# Madhumathimmiv_8-bit-breadboard-computer.net
KiCad netlist of a schematic drawn in Altium Designer
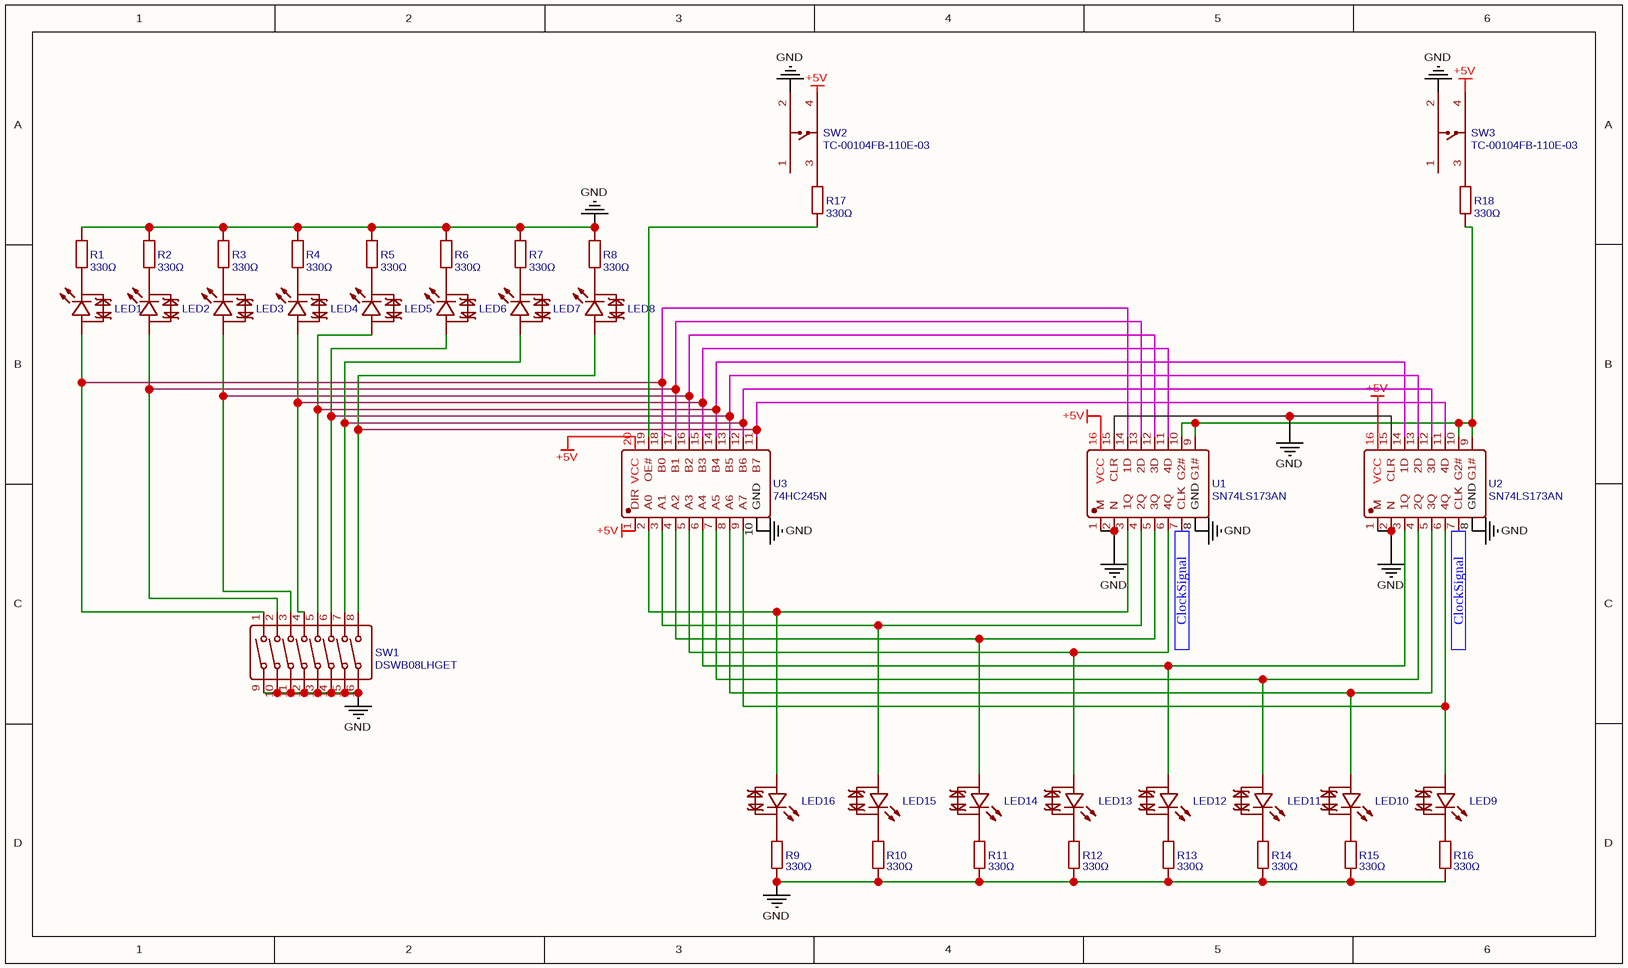
[diagram p0: Madhumathimmiv_8-bit-breadboard-computer-modules__schematic_Register__register.schdoc]

(export (version "E")
  (design (tool "Eeschema 10.0.6"))
  (components
    (comp (ref "LED1")
      (value "204-15UTC/S400-X9-L")
      (fields (field (name "MANUFACTURER") "EVERLIGHT(亿光)") (field (name "CONTRIBUTOR") "LCSC"))
      (libsource (lib "altium-import") (part "root_1_204-15UTC/S400-X9-L_"))
    )
    (comp (ref "LED2")
      (value "204-15UTC/S400-X9-L")
      (fields (field (name "MANUFACTURER") "EVERLIGHT(亿光)") (field (name "CONTRIBUTOR") "LCSC"))
      (libsource (lib "altium-import") (part "root_1_204-15UTC/S400-X9-L_"))
    )
    (comp (ref "LED3")
      (value "204-15UTC/S400-X9-L")
      (fields (field (name "MANUFACTURER") "EVERLIGHT(亿光)") (field (name "CONTRIBUTOR") "LCSC"))
      (libsource (lib "altium-import") (part "root_1_204-15UTC/S400-X9-L_"))
    )
    (comp (ref "LED4")
      (value "204-15UTC/S400-X9-L")
      (fields (field (name "MANUFACTURER") "EVERLIGHT(亿光)") (field (name "CONTRIBUTOR") "LCSC"))
      (libsource (lib "altium-import") (part "root_1_204-15UTC/S400-X9-L_"))
    )
    (comp (ref "LED5")
      (value "204-15UTC/S400-X9-L")
      (fields (field (name "MANUFACTURER") "EVERLIGHT(亿光)") (field (name "CONTRIBUTOR") "LCSC"))
      (libsource (lib "altium-import") (part "root_1_204-15UTC/S400-X9-L_"))
    )
    (comp (ref "LED6")
      (value "204-15UTC/S400-X9-L")
      (fields (field (name "MANUFACTURER") "EVERLIGHT(亿光)") (field (name "CONTRIBUTOR") "LCSC"))
      (libsource (lib "altium-import") (part "root_1_204-15UTC/S400-X9-L_"))
    )
    (comp (ref "LED7")
      (value "204-15UTC/S400-X9-L")
      (fields (field (name "MANUFACTURER") "EVERLIGHT(亿光)") (field (name "CONTRIBUTOR") "LCSC"))
      (libsource (lib "altium-import") (part "root_1_204-15UTC/S400-X9-L_"))
    )
    (comp (ref "LED8")
      (value "204-15UTC/S400-X9-L")
      (fields (field (name "MANUFACTURER") "EVERLIGHT(亿光)") (field (name "CONTRIBUTOR") "LCSC"))
      (libsource (lib "altium-import") (part "root_1_204-15UTC/S400-X9-L_"))
    )
    (comp (ref "LED9")
      (value "204-15UTC/S400-X9-L")
      (fields (field (name "MANUFACTURER") "EVERLIGHT(亿光)") (field (name "CONTRIBUTOR") "LCSC"))
      (libsource (lib "altium-import") (part "root_3_204-15UTC/S400-X9-L_"))
    )
    (comp (ref "LED10")
      (value "204-15UTC/S400-X9-L")
      (fields (field (name "MANUFACTURER") "EVERLIGHT(亿光)") (field (name "CONTRIBUTOR") "LCSC"))
      (libsource (lib "altium-import") (part "root_3_204-15UTC/S400-X9-L_"))
    )
    (comp (ref "LED11")
      (value "204-15UTC/S400-X9-L")
      (fields (field (name "MANUFACTURER") "EVERLIGHT(亿光)") (field (name "CONTRIBUTOR") "LCSC"))
      (libsource (lib "altium-import") (part "root_3_204-15UTC/S400-X9-L_"))
    )
    (comp (ref "LED12")
      (value "204-15UTC/S400-X9-L")
      (fields (field (name "MANUFACTURER") "EVERLIGHT(亿光)") (field (name "CONTRIBUTOR") "LCSC"))
      (libsource (lib "altium-import") (part "root_3_204-15UTC/S400-X9-L_"))
    )
    (comp (ref "LED13")
      (value "204-15UTC/S400-X9-L")
      (fields (field (name "MANUFACTURER") "EVERLIGHT(亿光)") (field (name "CONTRIBUTOR") "LCSC"))
      (libsource (lib "altium-import") (part "root_3_204-15UTC/S400-X9-L_"))
    )
    (comp (ref "LED14")
      (value "204-15UTC/S400-X9-L")
      (fields (field (name "MANUFACTURER") "EVERLIGHT(亿光)") (field (name "CONTRIBUTOR") "LCSC"))
      (libsource (lib "altium-import") (part "root_3_204-15UTC/S400-X9-L_"))
    )
    (comp (ref "LED15")
      (value "204-15UTC/S400-X9-L")
      (fields (field (name "MANUFACTURER") "EVERLIGHT(亿光)") (field (name "CONTRIBUTOR") "LCSC"))
      (libsource (lib "altium-import") (part "root_3_204-15UTC/S400-X9-L_"))
    )
    (comp (ref "LED16")
      (value "204-15UTC/S400-X9-L")
      (fields (field (name "MANUFACTURER") "EVERLIGHT(亿光)") (field (name "CONTRIBUTOR") "LCSC"))
      (libsource (lib "altium-import") (part "root_3_204-15UTC/S400-X9-L_"))
    )
    (comp (ref "R1")
      (value "330Ω")
      (fields
        (field (name "MANUFACTURER") "CCO(千志电子)")
        (field (name "MANUFACTURER PART") "MF1/2W-0.1Ω±1% T")
        (field (name "CONTRIBUTOR") "LCSC")
      )
      (libsource (lib "altium-import") (part "root_1_330Ω_"))
    )
    (comp (ref "R2")
      (value "330Ω")
      (fields
        (field (name "MANUFACTURER") "CCO(千志电子)")
        (field (name "MANUFACTURER PART") "MF1/2W-0.1Ω±1% T")
        (field (name "CONTRIBUTOR") "LCSC")
      )
      (libsource (lib "altium-import") (part "root_1_330Ω_"))
    )
    (comp (ref "R3")
      (value "330Ω")
      (fields
        (field (name "MANUFACTURER") "CCO(千志电子)")
        (field (name "MANUFACTURER PART") "MF1/2W-0.1Ω±1% T")
        (field (name "CONTRIBUTOR") "LCSC")
      )
      (libsource (lib "altium-import") (part "root_1_330Ω_"))
    )
    (comp (ref "R4")
      (value "330Ω")
      (fields
        (field (name "MANUFACTURER") "CCO(千志电子)")
        (field (name "MANUFACTURER PART") "MF1/2W-0.1Ω±1% T")
        (field (name "CONTRIBUTOR") "LCSC")
      )
      (libsource (lib "altium-import") (part "root_1_330Ω_"))
    )
    (comp (ref "R5")
      (value "330Ω")
      (fields
        (field (name "MANUFACTURER") "CCO(千志电子)")
        (field (name "MANUFACTURER PART") "MF1/2W-0.1Ω±1% T")
        (field (name "CONTRIBUTOR") "LCSC")
      )
      (libsource (lib "altium-import") (part "root_1_330Ω_"))
    )
    (comp (ref "R6")
      (value "330Ω")
      (fields
        (field (name "MANUFACTURER") "CCO(千志电子)")
        (field (name "MANUFACTURER PART") "MF1/2W-0.1Ω±1% T")
        (field (name "CONTRIBUTOR") "LCSC")
      )
      (libsource (lib "altium-import") (part "root_1_330Ω_"))
    )
    (comp (ref "R7")
      (value "330Ω")
      (fields
        (field (name "MANUFACTURER") "CCO(千志电子)")
        (field (name "MANUFACTURER PART") "MF1/2W-0.1Ω±1% T")
        (field (name "CONTRIBUTOR") "LCSC")
      )
      (libsource (lib "altium-import") (part "root_1_330Ω_"))
    )
    (comp (ref "R8")
      (value "330Ω")
      (fields
        (field (name "MANUFACTURER") "CCO(千志电子)")
        (field (name "MANUFACTURER PART") "MF1/2W-0.1Ω±1% T")
        (field (name "CONTRIBUTOR") "LCSC")
      )
      (libsource (lib "altium-import") (part "root_1_330Ω_"))
    )
    (comp (ref "R9")
      (value "330Ω")
      (fields
        (field (name "MANUFACTURER") "CCO(千志电子)")
        (field (name "MANUFACTURER PART") "MF1/2W-0.1Ω±1% T")
        (field (name "CONTRIBUTOR") "LCSC")
      )
      (libsource (lib "altium-import") (part "root_3_330Ω_"))
    )
    (comp (ref "R10")
      (value "330Ω")
      (fields
        (field (name "MANUFACTURER") "CCO(千志电子)")
        (field (name "MANUFACTURER PART") "MF1/2W-0.1Ω±1% T")
        (field (name "CONTRIBUTOR") "LCSC")
      )
      (libsource (lib "altium-import") (part "root_3_330Ω_"))
    )
    (comp (ref "R11")
      (value "330Ω")
      (fields
        (field (name "MANUFACTURER") "CCO(千志电子)")
        (field (name "MANUFACTURER PART") "MF1/2W-0.1Ω±1% T")
        (field (name "CONTRIBUTOR") "LCSC")
      )
      (libsource (lib "altium-import") (part "root_3_330Ω_"))
    )
    (comp (ref "R12")
      (value "330Ω")
      (fields
        (field (name "MANUFACTURER") "CCO(千志电子)")
        (field (name "MANUFACTURER PART") "MF1/2W-0.1Ω±1% T")
        (field (name "CONTRIBUTOR") "LCSC")
      )
      (libsource (lib "altium-import") (part "root_3_330Ω_"))
    )
    (comp (ref "R13")
      (value "330Ω")
      (fields
        (field (name "MANUFACTURER") "CCO(千志电子)")
        (field (name "MANUFACTURER PART") "MF1/2W-0.1Ω±1% T")
        (field (name "CONTRIBUTOR") "LCSC")
      )
      (libsource (lib "altium-import") (part "root_3_330Ω_"))
    )
    (comp (ref "R14")
      (value "330Ω")
      (fields
        (field (name "MANUFACTURER") "CCO(千志电子)")
        (field (name "MANUFACTURER PART") "MF1/2W-0.1Ω±1% T")
        (field (name "CONTRIBUTOR") "LCSC")
      )
      (libsource (lib "altium-import") (part "root_3_330Ω_"))
    )
    (comp (ref "R15")
      (value "330Ω")
      (fields
        (field (name "MANUFACTURER") "CCO(千志电子)")
        (field (name "MANUFACTURER PART") "MF1/2W-0.1Ω±1% T")
        (field (name "CONTRIBUTOR") "LCSC")
      )
      (libsource (lib "altium-import") (part "root_3_330Ω_"))
    )
    (comp (ref "R16")
      (value "330Ω")
      (fields
        (field (name "MANUFACTURER") "CCO(千志电子)")
        (field (name "MANUFACTURER PART") "MF1/2W-0.1Ω±1% T")
        (field (name "CONTRIBUTOR") "LCSC")
      )
      (libsource (lib "altium-import") (part "root_3_330Ω_"))
    )
    (comp (ref "R17")
      (value "330Ω")
      (fields
        (field (name "MANUFACTURER") "CCO(千志电子)")
        (field (name "MANUFACTURER PART") "MF1/2W-0.1Ω±1% T")
        (field (name "CONTRIBUTOR") "LCSC")
      )
      (libsource (lib "altium-import") (part "root_1_330Ω_"))
    )
    (comp (ref "R18")
      (value "330Ω")
      (fields
        (field (name "MANUFACTURER") "CCO(千志电子)")
        (field (name "MANUFACTURER PART") "MF1/2W-0.1Ω±1% T")
        (field (name "CONTRIBUTOR") "LCSC")
      )
      (libsource (lib "altium-import") (part "root_1_330Ω_"))
    )
    (comp (ref "SW1")
      (value "DSWB08LHGET")
      (fields (field (name "MANUFACTURER") "YE") (field (name "CONTRIBUTOR") "LCSC"))
      (libsource (lib "altium-import") (part "root_0_DSWB08LHGET_"))
    )
    (comp (ref "SW2")
      (value "TC-00104FB-110E-03")
      (fields (field (name "MANUFACTURER") "HOOYA(皓宇电子)") (field (name "CONTRIBUTOR") "lcsc"))
      (libsource (lib "altium-import") (part "root_1_TC-00104FB-110E-03_"))
    )
    (comp (ref "SW3")
      (value "TC-00104FB-110E-03")
      (fields (field (name "MANUFACTURER") "HOOYA(皓宇电子)") (field (name "CONTRIBUTOR") "lcsc"))
      (libsource (lib "altium-import") (part "root_1_TC-00104FB-110E-03_"))
    )
    (comp (ref "U1")
      (value "SN74LS173AN")
      (fields (field (name "MANUFACTURER") "TI(德州仪器)") (field (name "CONTRIBUTOR") "LCSC"))
      (libsource (lib "altium-import") (part "root_1_SN74LS173AN_"))
    )
    (comp (ref "U2")
      (value "SN74LS173AN")
      (fields (field (name "MANUFACTURER") "TI(德州仪器)") (field (name "CONTRIBUTOR") "LCSC"))
      (libsource (lib "altium-import") (part "root_1_SN74LS173AN_"))
    )
    (comp (ref "U3")
      (value "74HC245N")
      (fields (field (name "MANUFACTURER") "HGSEMI(华冠)") (field (name "CONTRIBUTOR") "LCSC"))
      (libsource (lib "altium-import") (part "root_1_74HC245N_"))
    )
  )
  (nets
    (net (code "1") (name "+5V") (class "Default")
      (node (ref "SW3") (pin "4") (pinfunction "4_4") (pintype "passive"))
      (node (ref "U1") (pin "16") (pinfunction "VCC_16") (pintype "passive"))
      (node (ref "U2") (pin "16") (pinfunction "VCC_16") (pintype "passive"))
      (node (ref "U3") (pin "1") (pinfunction "DIR_1") (pintype "passive"))
      (node (ref "U3") (pin "20") (pinfunction "VCC_20") (pintype "passive"))
    )
    (net (code "2") (name "/ClockSignal") (class "Default")
      (node (ref "U1") (pin "7") (pinfunction "CLK_7") (pintype "passive"))
      (node (ref "U2") (pin "7") (pinfunction "CLK_7") (pintype "passive"))
    )
    (net (code "3") (name "GND") (class "Default")
      (node (ref "R1") (pin "2") (pinfunction "2_2") (pintype "passive"))
      (node (ref "R10") (pin "2") (pinfunction "2_2") (pintype "passive"))
      (node (ref "R11") (pin "2") (pinfunction "2_2") (pintype "passive"))
      (node (ref "R12") (pin "2") (pinfunction "2_2") (pintype "passive"))
      (node (ref "R13") (pin "2") (pinfunction "2_2") (pintype "passive"))
      (node (ref "R14") (pin "2") (pinfunction "2_2") (pintype "passive"))
      (node (ref "R15") (pin "2") (pinfunction "2_2") (pintype "passive"))
      (node (ref "R16") (pin "2") (pinfunction "2_2") (pintype "passive"))
      (node (ref "R2") (pin "2") (pinfunction "2_2") (pintype "passive"))
      (node (ref "R3") (pin "2") (pinfunction "2_2") (pintype "passive"))
      (node (ref "R4") (pin "2") (pinfunction "2_2") (pintype "passive"))
      (node (ref "R5") (pin "2") (pinfunction "2_2") (pintype "passive"))
      (node (ref "R6") (pin "2") (pinfunction "2_2") (pintype "passive"))
      (node (ref "R7") (pin "2") (pinfunction "2_2") (pintype "passive"))
      (node (ref "R8") (pin "2") (pinfunction "2_2") (pintype "passive"))
      (node (ref "R9") (pin "2") (pinfunction "2_2") (pintype "passive"))
      (node (ref "SW1") (pin "10") (pinfunction "10_10") (pintype "passive"))
      (node (ref "SW1") (pin "11") (pinfunction "11_11") (pintype "passive"))
      (node (ref "SW1") (pin "12") (pinfunction "12_12") (pintype "passive"))
      (node (ref "SW1") (pin "13") (pinfunction "13_13") (pintype "passive"))
      (node (ref "SW1") (pin "14") (pinfunction "14_14") (pintype "passive"))
      (node (ref "SW1") (pin "15") (pinfunction "15_15") (pintype "passive"))
      (node (ref "SW1") (pin "16") (pinfunction "16_16") (pintype "passive"))
      (node (ref "SW1") (pin "9") (pinfunction "9_9") (pintype "passive"))
      (node (ref "SW2") (pin "2") (pinfunction "2_2") (pintype "passive"))
      (node (ref "SW3") (pin "2") (pinfunction "2_2") (pintype "passive"))
      (node (ref "U1") (pin "1") (pinfunction "M_1") (pintype "passive"))
      (node (ref "U1") (pin "15") (pinfunction "CLR_15") (pintype "passive"))
      (node (ref "U1") (pin "2") (pinfunction "N_2") (pintype "passive"))
      (node (ref "U1") (pin "8") (pinfunction "GND_8") (pintype "passive"))
      (node (ref "U2") (pin "1") (pinfunction "M_1") (pintype "passive"))
      (node (ref "U2") (pin "15") (pinfunction "CLR_15") (pintype "passive"))
      (node (ref "U2") (pin "2") (pinfunction "N_2") (pintype "passive"))
      (node (ref "U2") (pin "8") (pinfunction "GND_8") (pintype "passive"))
      (node (ref "U3") (pin "10") (pinfunction "GND_10") (pintype "passive"))
    )
    (net (code "4") (name "Net-(LED1-A)") (class "Default")
      (node (ref "LED1") (pin "1") (pinfunction "A_1") (pintype "passive"))
      (node (ref "SW1") (pin "1") (pinfunction "1_1") (pintype "passive"))
      (node (ref "U1") (pin "14") (pinfunction "1D_14") (pintype "passive"))
      (node (ref "U3") (pin "18") (pinfunction "B0_18") (pintype "passive"))
    )
    (net (code "5") (name "Net-(LED1-C)") (class "Default")
      (node (ref "LED1") (pin "2") (pinfunction "C_2") (pintype "passive"))
      (node (ref "R1") (pin "1") (pinfunction "1_1") (pintype "passive"))
    )
    (net (code "6") (name "Net-(LED2-A)") (class "Default")
      (node (ref "LED2") (pin "1") (pinfunction "A_1") (pintype "passive"))
      (node (ref "SW1") (pin "2") (pinfunction "2_2") (pintype "passive"))
      (node (ref "U1") (pin "13") (pinfunction "2D_13") (pintype "passive"))
      (node (ref "U3") (pin "17") (pinfunction "B1_17") (pintype "passive"))
    )
    (net (code "7") (name "Net-(LED2-C)") (class "Default")
      (node (ref "LED2") (pin "2") (pinfunction "C_2") (pintype "passive"))
      (node (ref "R2") (pin "1") (pinfunction "1_1") (pintype "passive"))
    )
    (net (code "8") (name "Net-(LED3-A)") (class "Default")
      (node (ref "LED3") (pin "1") (pinfunction "A_1") (pintype "passive"))
      (node (ref "SW1") (pin "3") (pinfunction "3_3") (pintype "passive"))
      (node (ref "U1") (pin "12") (pinfunction "3D_12") (pintype "passive"))
      (node (ref "U3") (pin "16") (pinfunction "B2_16") (pintype "passive"))
    )
    (net (code "9") (name "Net-(LED3-C)") (class "Default")
      (node (ref "LED3") (pin "2") (pinfunction "C_2") (pintype "passive"))
      (node (ref "R3") (pin "1") (pinfunction "1_1") (pintype "passive"))
    )
    (net (code "10") (name "Net-(LED4-A)") (class "Default")
      (node (ref "LED4") (pin "1") (pinfunction "A_1") (pintype "passive"))
      (node (ref "SW1") (pin "4") (pinfunction "4_4") (pintype "passive"))
      (node (ref "U1") (pin "11") (pinfunction "4D_11") (pintype "passive"))
      (node (ref "U3") (pin "15") (pinfunction "B3_15") (pintype "passive"))
    )
    (net (code "11") (name "Net-(LED4-C)") (class "Default")
      (node (ref "LED4") (pin "2") (pinfunction "C_2") (pintype "passive"))
      (node (ref "R4") (pin "1") (pinfunction "1_1") (pintype "passive"))
    )
    (net (code "12") (name "Net-(LED5-A)") (class "Default")
      (node (ref "LED5") (pin "1") (pinfunction "A_1") (pintype "passive"))
      (node (ref "SW1") (pin "5") (pinfunction "5_5") (pintype "passive"))
      (node (ref "U2") (pin "14") (pinfunction "1D_14") (pintype "passive"))
      (node (ref "U3") (pin "14") (pinfunction "B4_14") (pintype "passive"))
    )
    (net (code "13") (name "Net-(LED5-C)") (class "Default")
      (node (ref "LED5") (pin "2") (pinfunction "C_2") (pintype "passive"))
      (node (ref "R5") (pin "1") (pinfunction "1_1") (pintype "passive"))
    )
    (net (code "14") (name "Net-(LED6-A)") (class "Default")
      (node (ref "LED6") (pin "1") (pinfunction "A_1") (pintype "passive"))
      (node (ref "SW1") (pin "6") (pinfunction "6_6") (pintype "passive"))
      (node (ref "U2") (pin "13") (pinfunction "2D_13") (pintype "passive"))
      (node (ref "U3") (pin "13") (pinfunction "B5_13") (pintype "passive"))
    )
    (net (code "15") (name "Net-(LED6-C)") (class "Default")
      (node (ref "LED6") (pin "2") (pinfunction "C_2") (pintype "passive"))
      (node (ref "R6") (pin "1") (pinfunction "1_1") (pintype "passive"))
    )
    (net (code "16") (name "Net-(LED7-A)") (class "Default")
      (node (ref "LED7") (pin "1") (pinfunction "A_1") (pintype "passive"))
      (node (ref "SW1") (pin "7") (pinfunction "7_7") (pintype "passive"))
      (node (ref "U2") (pin "12") (pinfunction "3D_12") (pintype "passive"))
      (node (ref "U3") (pin "12") (pinfunction "B6_12") (pintype "passive"))
    )
    (net (code "17") (name "Net-(LED7-C)") (class "Default")
      (node (ref "LED7") (pin "2") (pinfunction "C_2") (pintype "passive"))
      (node (ref "R7") (pin "1") (pinfunction "1_1") (pintype "passive"))
    )
    (net (code "18") (name "Net-(LED8-A)") (class "Default")
      (node (ref "LED8") (pin "1") (pinfunction "A_1") (pintype "passive"))
      (node (ref "SW1") (pin "8") (pinfunction "8_8") (pintype "passive"))
      (node (ref "U2") (pin "11") (pinfunction "4D_11") (pintype "passive"))
      (node (ref "U3") (pin "11") (pinfunction "B7_11") (pintype "passive"))
    )
    (net (code "19") (name "Net-(LED8-C)") (class "Default")
      (node (ref "LED8") (pin "2") (pinfunction "C_2") (pintype "passive"))
      (node (ref "R8") (pin "1") (pinfunction "1_1") (pintype "passive"))
    )
    (net (code "20") (name "Net-(LED9-A)") (class "Default")
      (node (ref "LED9") (pin "1") (pinfunction "A_1") (pintype "passive"))
      (node (ref "U2") (pin "6") (pinfunction "4Q_6") (pintype "passive"))
      (node (ref "U3") (pin "9") (pinfunction "A7_9") (pintype "passive"))
    )
    (net (code "21") (name "Net-(LED9-C)") (class "Default")
      (node (ref "LED9") (pin "2") (pinfunction "C_2") (pintype "passive"))
      (node (ref "R16") (pin "1") (pinfunction "1_1") (pintype "passive"))
    )
    (net (code "22") (name "Net-(LED10-A)") (class "Default")
      (node (ref "LED10") (pin "1") (pinfunction "A_1") (pintype "passive"))
      (node (ref "U2") (pin "5") (pinfunction "3Q_5") (pintype "passive"))
      (node (ref "U3") (pin "8") (pinfunction "A6_8") (pintype "passive"))
    )
    (net (code "23") (name "Net-(LED10-C)") (class "Default")
      (node (ref "LED10") (pin "2") (pinfunction "C_2") (pintype "passive"))
      (node (ref "R15") (pin "1") (pinfunction "1_1") (pintype "passive"))
    )
    (net (code "24") (name "Net-(LED11-A)") (class "Default")
      (node (ref "LED11") (pin "1") (pinfunction "A_1") (pintype "passive"))
      (node (ref "U2") (pin "4") (pinfunction "2Q_4") (pintype "passive"))
      (node (ref "U3") (pin "7") (pinfunction "A5_7") (pintype "passive"))
    )
    (net (code "25") (name "Net-(LED11-C)") (class "Default")
      (node (ref "LED11") (pin "2") (pinfunction "C_2") (pintype "passive"))
      (node (ref "R14") (pin "1") (pinfunction "1_1") (pintype "passive"))
    )
    (net (code "26") (name "Net-(LED12-A)") (class "Default")
      (node (ref "LED12") (pin "1") (pinfunction "A_1") (pintype "passive"))
      (node (ref "U2") (pin "3") (pinfunction "1Q_3") (pintype "passive"))
      (node (ref "U3") (pin "6") (pinfunction "A4_6") (pintype "passive"))
    )
    (net (code "27") (name "Net-(LED12-C)") (class "Default")
      (node (ref "LED12") (pin "2") (pinfunction "C_2") (pintype "passive"))
      (node (ref "R13") (pin "1") (pinfunction "1_1") (pintype "passive"))
    )
    (net (code "28") (name "Net-(LED13-A)") (class "Default")
      (node (ref "LED13") (pin "1") (pinfunction "A_1") (pintype "passive"))
      (node (ref "U1") (pin "6") (pinfunction "4Q_6") (pintype "passive"))
      (node (ref "U3") (pin "5") (pinfunction "A3_5") (pintype "passive"))
    )
    (net (code "29") (name "Net-(LED13-C)") (class "Default")
      (node (ref "LED13") (pin "2") (pinfunction "C_2") (pintype "passive"))
      (node (ref "R12") (pin "1") (pinfunction "1_1") (pintype "passive"))
    )
    (net (code "30") (name "Net-(LED14-A)") (class "Default")
      (node (ref "LED14") (pin "1") (pinfunction "A_1") (pintype "passive"))
      (node (ref "U1") (pin "5") (pinfunction "3Q_5") (pintype "passive"))
      (node (ref "U3") (pin "4") (pinfunction "A2_4") (pintype "passive"))
    )
    (net (code "31") (name "Net-(LED14-C)") (class "Default")
      (node (ref "LED14") (pin "2") (pinfunction "C_2") (pintype "passive"))
      (node (ref "R11") (pin "1") (pinfunction "1_1") (pintype "passive"))
    )
    (net (code "32") (name "Net-(LED15-A)") (class "Default")
      (node (ref "LED15") (pin "1") (pinfunction "A_1") (pintype "passive"))
      (node (ref "U1") (pin "4") (pinfunction "2Q_4") (pintype "passive"))
      (node (ref "U3") (pin "3") (pinfunction "A1_3") (pintype "passive"))
    )
    (net (code "33") (name "Net-(LED15-C)") (class "Default")
      (node (ref "LED15") (pin "2") (pinfunction "C_2") (pintype "passive"))
      (node (ref "R10") (pin "1") (pinfunction "1_1") (pintype "passive"))
    )
    (net (code "34") (name "Net-(LED16-A)") (class "Default")
      (node (ref "LED16") (pin "1") (pinfunction "A_1") (pintype "passive"))
      (node (ref "U1") (pin "3") (pinfunction "1Q_3") (pintype "passive"))
      (node (ref "U3") (pin "2") (pinfunction "A0_2") (pintype "passive"))
    )
    (net (code "35") (name "Net-(LED16-C)") (class "Default")
      (node (ref "LED16") (pin "2") (pinfunction "C_2") (pintype "passive"))
      (node (ref "R9") (pin "1") (pinfunction "1_1") (pintype "passive"))
    )
    (net (code "36") (name "Net-(R17-Pad2)") (class "Default")
      (node (ref "R17") (pin "2") (pinfunction "2_2") (pintype "passive"))
      (node (ref "SW2") (pin "3") (pinfunction "3_3") (pintype "passive"))
    )
    (net (code "37") (name "Net-(R18-Pad2)") (class "Default")
      (node (ref "R18") (pin "2") (pinfunction "2_2") (pintype "passive"))
      (node (ref "SW3") (pin "3") (pinfunction "3_3") (pintype "passive"))
    )
    (net (code "38") (name "Net-(U1-G1#)") (class "Default")
      (node (ref "R18") (pin "1") (pinfunction "1_1") (pintype "passive"))
      (node (ref "U1") (pin "10") (pinfunction "G2#_10") (pintype "passive"))
      (node (ref "U1") (pin "9") (pinfunction "G1#_9") (pintype "passive"))
      (node (ref "U2") (pin "10") (pinfunction "G2#_10") (pintype "passive"))
      (node (ref "U2") (pin "9") (pinfunction "G1#_9") (pintype "passive"))
    )
    (net (code "39") (name "Net-(U3-OE#)") (class "Default")
      (node (ref "R17") (pin "1") (pinfunction "1_1") (pintype "passive"))
      (node (ref "U3") (pin "19") (pinfunction "OE#_19") (pintype "passive"))
    )
    (net (code "40") (name "unconnected-(SW2-Pad1)") (class "Default")
      (node (ref "SW2") (pin "1") (pinfunction "1_1") (pintype "passive"))
    )
    (net (code "41") (name "unconnected-(SW2-Pad4)") (class "Default")
      (node (ref "SW2") (pin "4") (pinfunction "4_4") (pintype "passive"))
    )
    (net (code "42") (name "unconnected-(SW3-Pad1)") (class "Default")
      (node (ref "SW3") (pin "1") (pinfunction "1_1") (pintype "passive"))
    )
  )
)
